# driver.net
KiCad netlist of a schematic drawn in EAGLE
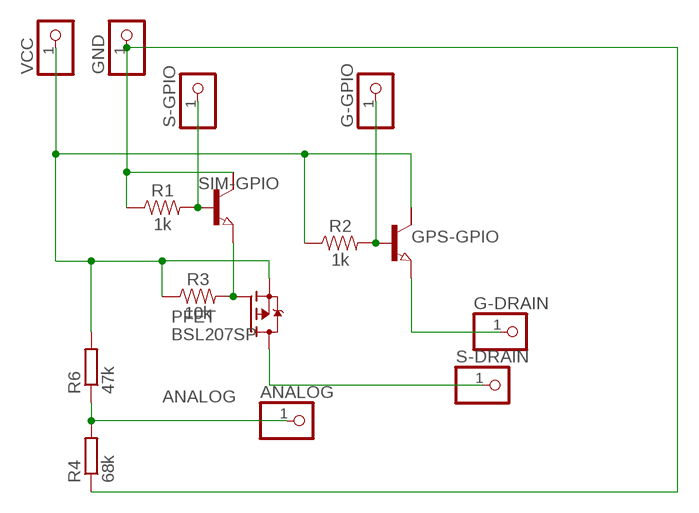
[diagram p0: schematic, sheet 1]

(export (version "E")
  (design (tool "Eeschema 10.0.6"))
  (components
    (comp (ref "ANALOG")
      (value "PINHD-1X1")
      (footprint "eagle-import:1X01")
      (libsource (lib "eagle-import") (part "PINHD-1X1"))
    )
    (comp (ref "G-DRAIN")
      (value "PINHD-1X1")
      (footprint "eagle-import:1X01")
      (libsource (lib "eagle-import") (part "PINHD-1X1"))
    )
    (comp (ref "G-GPIO")
      (value "PINHD-1X1")
      (footprint "eagle-import:1X01")
      (libsource (lib "eagle-import") (part "PINHD-1X1"))
    )
    (comp (ref "GND")
      (value "PINHD-1X1")
      (footprint "eagle-import:1X01")
      (libsource (lib "eagle-import") (part "PINHD-1X1"))
    )
    (comp (ref "GPS-GPIO")
      (value "NPN-TRANSISTIOR-2COLSOT89")
      (footprint "eagle-import:SOT89")
      (libsource (lib "eagle-import") (part "NPN-TRANSISTIOR-2COLSOT89"))
    )
    (comp (ref "PFET")
      (value "BSL207SP")
      (footprint "eagle-import:SC74_INFINEON")
      (libsource (lib "eagle-import") (part "BSL207SP"))
    )
    (comp (ref "R1")
      (value "1k")
      (footprint "eagle-import:0603")
      (libsource (lib "eagle-import") (part "10KOHM-0603-1/10W-1%"))
    )
    (comp (ref "R2")
      (value "1k")
      (footprint "eagle-import:0603")
      (libsource (lib "eagle-import") (part "10KOHM-0603-1/10W-1%"))
    )
    (comp (ref "R3")
      (value "10k")
      (footprint "eagle-import:0603")
      (libsource (lib "eagle-import") (part "10KOHM-0603-1/10W-1%"))
    )
    (comp (ref "R4")
      (value "68k")
      (footprint "eagle-import:0204_7")
      (libsource (lib "eagle-import") (part "R-EU_0204/7"))
    )
    (comp (ref "R6")
      (value "47k")
      (footprint "eagle-import:0204_7")
      (libsource (lib "eagle-import") (part "R-EU_0204/7"))
    )
    (comp (ref "S-DRAIN")
      (value "PINHD-1X1")
      (footprint "eagle-import:1X01")
      (libsource (lib "eagle-import") (part "PINHD-1X1"))
    )
    (comp (ref "S-GPIO")
      (value "PINHD-1X1")
      (footprint "eagle-import:1X01")
      (libsource (lib "eagle-import") (part "PINHD-1X1"))
    )
    (comp (ref "SIM-GPIO")
      (value "NPN-TRANSISTIOR-2COLSOT89")
      (footprint "eagle-import:SOT89")
      (libsource (lib "eagle-import") (part "NPN-TRANSISTIOR-2COLSOT89"))
    )
    (comp (ref "VCC")
      (value "PINHD-1X1")
      (footprint "eagle-import:1X01")
      (libsource (lib "eagle-import") (part "PINHD-1X1"))
    )
  )
  (nets
    (net (code "1") (name "/ANALOG") (class "Default")
      (node (ref "ANALOG") (pin "1") (pinfunction "1_1") (pintype "passive"))
      (node (ref "R4") (pin "2") (pinfunction "2_2") (pintype "passive"))
      (node (ref "R6") (pin "1") (pinfunction "1_1") (pintype "passive"))
    )
    (net (code "2") (name "Net-(GPS-GPIO-B)") (class "Default")
      (node (ref "G-GPIO") (pin "1") (pinfunction "1_1") (pintype "passive"))
      (node (ref "GPS-GPIO") (pin "1") (pinfunction "B_1") (pintype "passive"))
      (node (ref "R2") (pin "2") (pinfunction "2_2") (pintype "passive"))
    )
    (net (code "3") (name "Net-(GPS-GPIO-C)") (class "Default")
      (node (ref "GPS-GPIO") (pin "2") (pinfunction "C_2") (pintype "passive"))
      (node (ref "PFET") (pin "4") (pinfunction "S_4") (pintype "passive"))
      (node (ref "R2") (pin "1") (pinfunction "1_1") (pintype "passive"))
      (node (ref "R3") (pin "1") (pinfunction "1_1") (pintype "passive"))
      (node (ref "R6") (pin "2") (pinfunction "2_2") (pintype "passive"))
      (node (ref "VCC") (pin "1") (pinfunction "1_1") (pintype "passive"))
    )
    (net (code "4") (name "Net-(GPS-GPIO-E)") (class "Default")
      (node (ref "G-DRAIN") (pin "1") (pinfunction "1_1") (pintype "passive"))
      (node (ref "GPS-GPIO") (pin "3") (pinfunction "E_3") (pintype "passive"))
    )
    (net (code "5") (name "Net-(PFET-D-Pad1)") (class "Default")
      (node (ref "PFET") (pin "1") (pinfunction "D_1") (pintype "passive"))
      (node (ref "PFET") (pin "2") (pinfunction "D_2") (pintype "passive"))
      (node (ref "PFET") (pin "5") (pinfunction "D_5") (pintype "passive"))
      (node (ref "PFET") (pin "6") (pinfunction "D_6") (pintype "passive"))
      (node (ref "S-DRAIN") (pin "1") (pinfunction "1_1") (pintype "passive"))
    )
    (net (code "6") (name "Net-(PFET-G)") (class "Default")
      (node (ref "PFET") (pin "3") (pinfunction "G_3") (pintype "passive"))
      (node (ref "R3") (pin "2") (pinfunction "2_2") (pintype "passive"))
      (node (ref "SIM-GPIO") (pin "3") (pinfunction "E_3") (pintype "passive"))
    )
    (net (code "7") (name "Net-(SIM-GPIO-B)") (class "Default")
      (node (ref "R1") (pin "2") (pinfunction "2_2") (pintype "passive"))
      (node (ref "S-GPIO") (pin "1") (pinfunction "1_1") (pintype "passive"))
      (node (ref "SIM-GPIO") (pin "1") (pinfunction "B_1") (pintype "passive"))
    )
    (net (code "8") (name "Net-(SIM-GPIO-C)") (class "Default")
      (node (ref "GND") (pin "1") (pinfunction "1_1") (pintype "passive"))
      (node (ref "R1") (pin "1") (pinfunction "1_1") (pintype "passive"))
      (node (ref "R4") (pin "1") (pinfunction "1_1") (pintype "passive"))
      (node (ref "SIM-GPIO") (pin "2") (pinfunction "C_2") (pintype "passive"))
    )
    (net (code "9") (name "unconnected-(GPS-GPIO-C{slash}-Pad2@1)") (class "Default")
      (node (ref "GPS-GPIO") (pin "2@1") (pinfunction "C/_2@1") (pintype "passive"))
    )
    (net (code "10") (name "unconnected-(SIM-GPIO-C{slash}-Pad2@1)") (class "Default")
      (node (ref "SIM-GPIO") (pin "2@1") (pinfunction "C/_2@1") (pintype "passive"))
    )
  )
)
